# 612_jetracer_esp32s3_030009.net
KiCad netlist of a schematic drawn in EAGLE
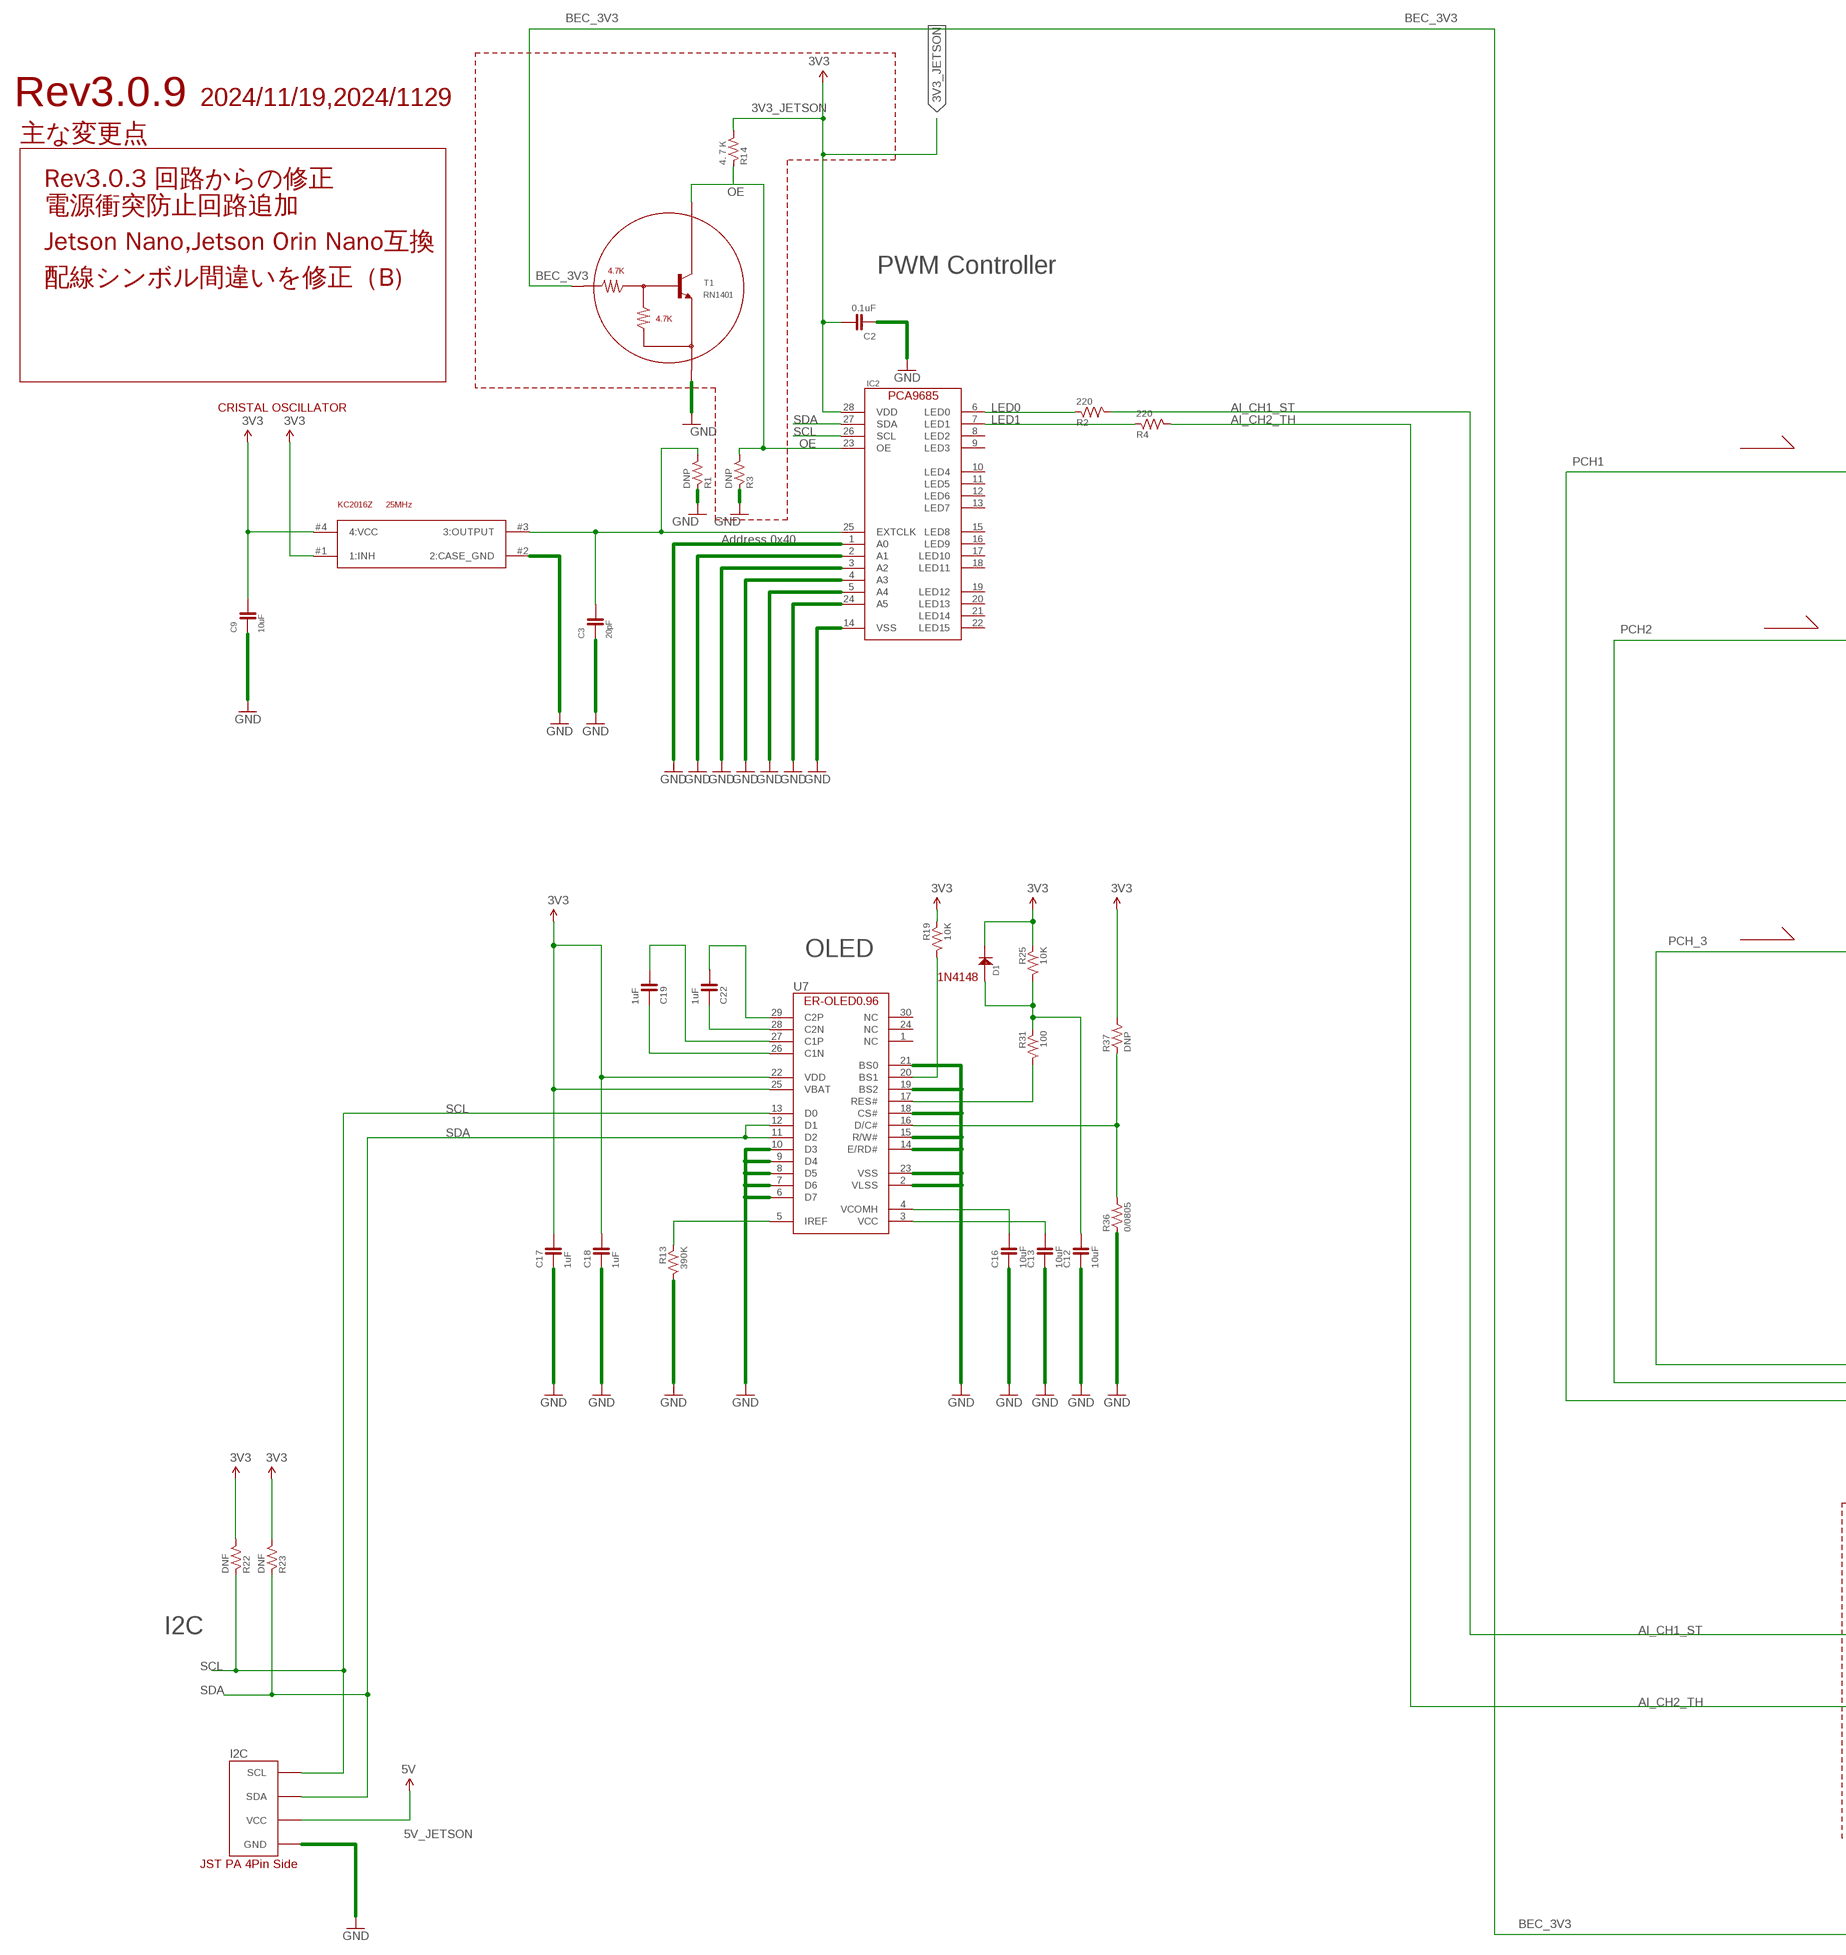
[diagram p0: schematic, sheet 1, part 1 of 3]
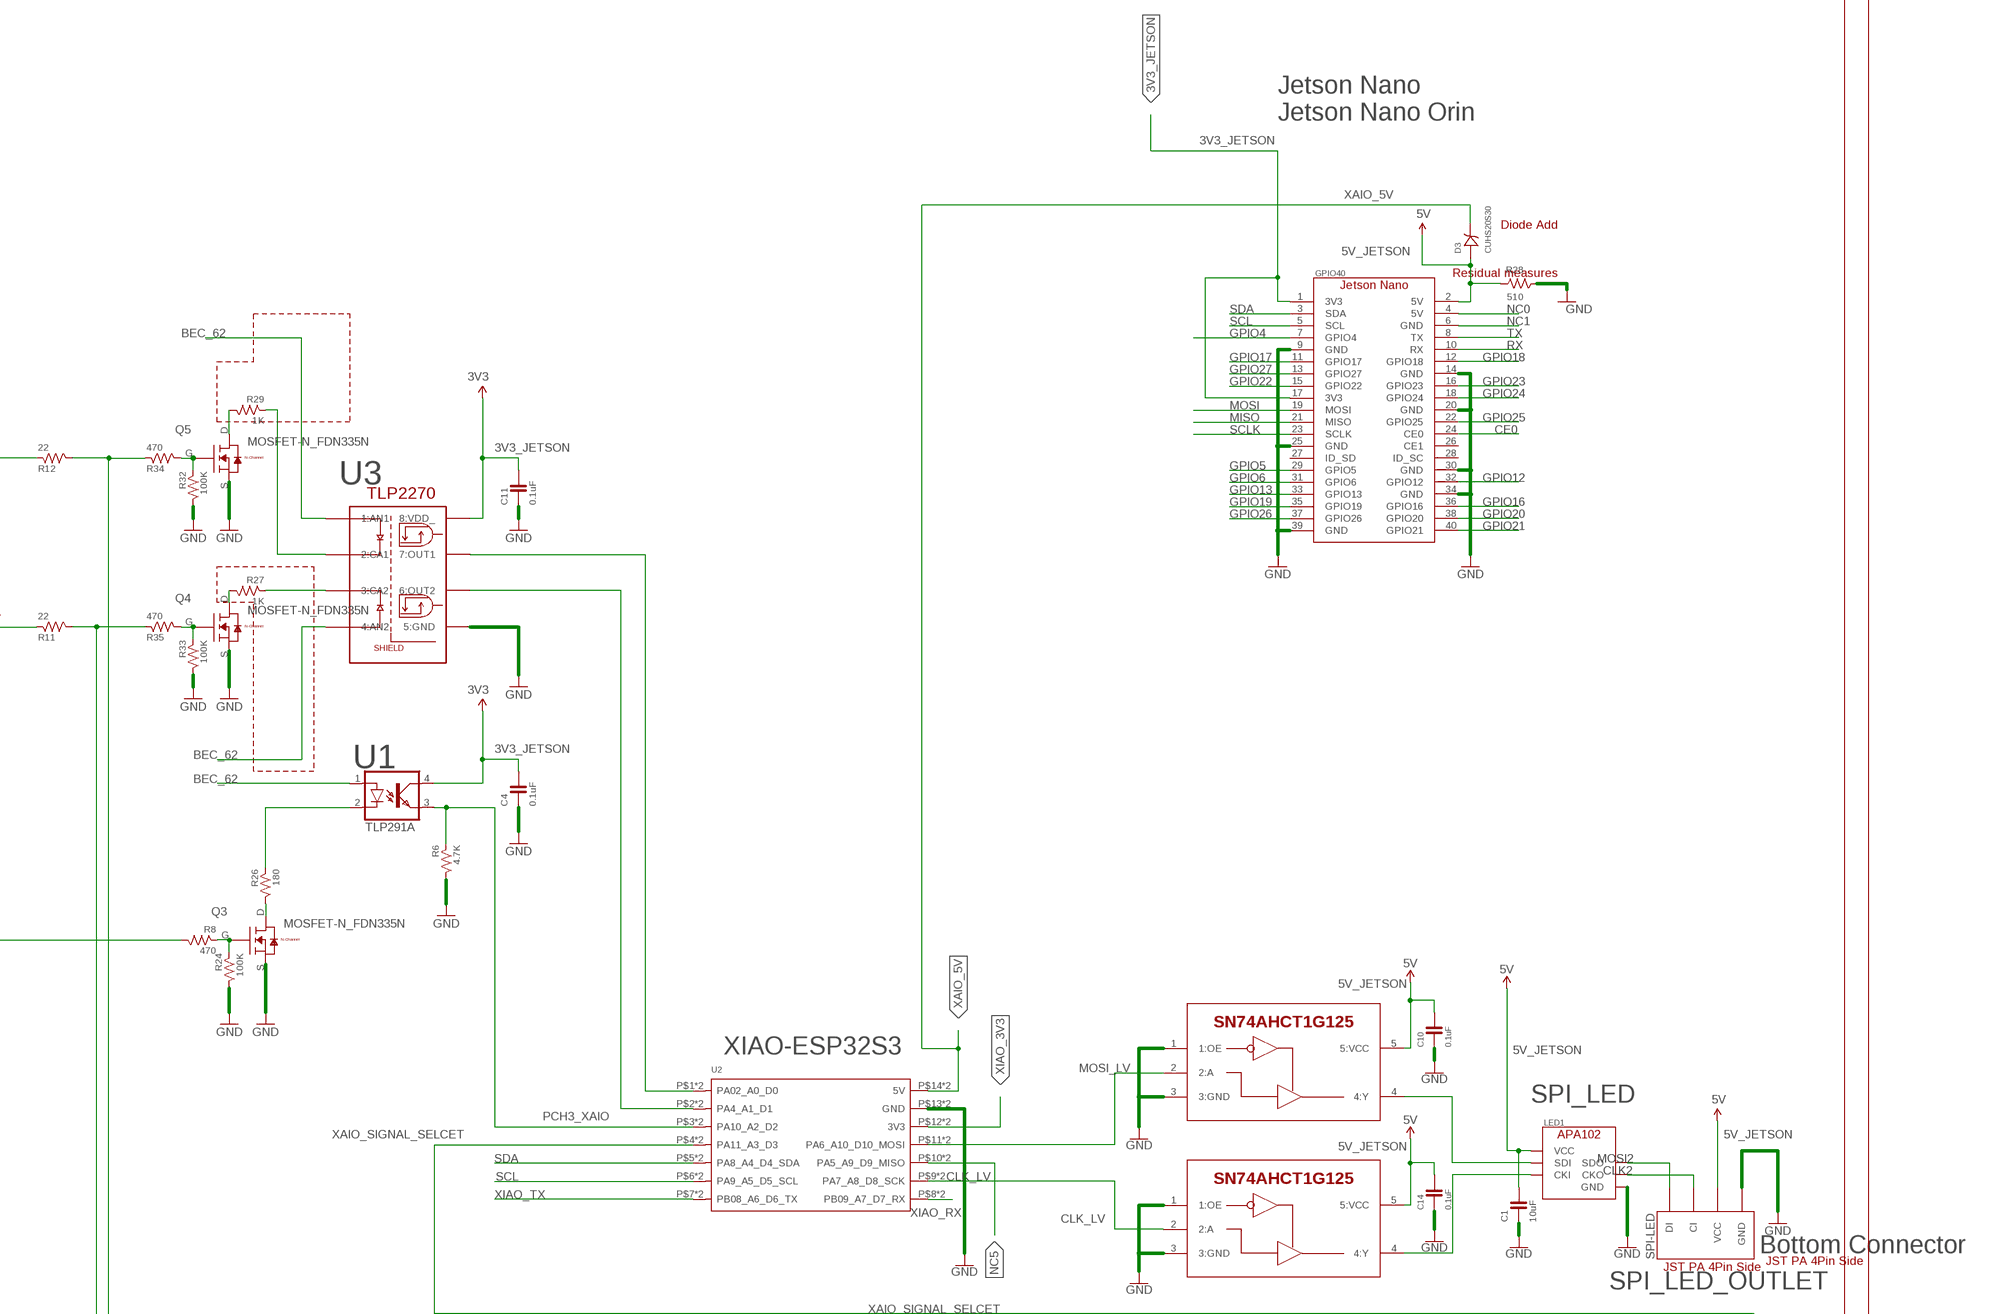
[diagram p1: schematic, sheet 1, part 2 of 3]
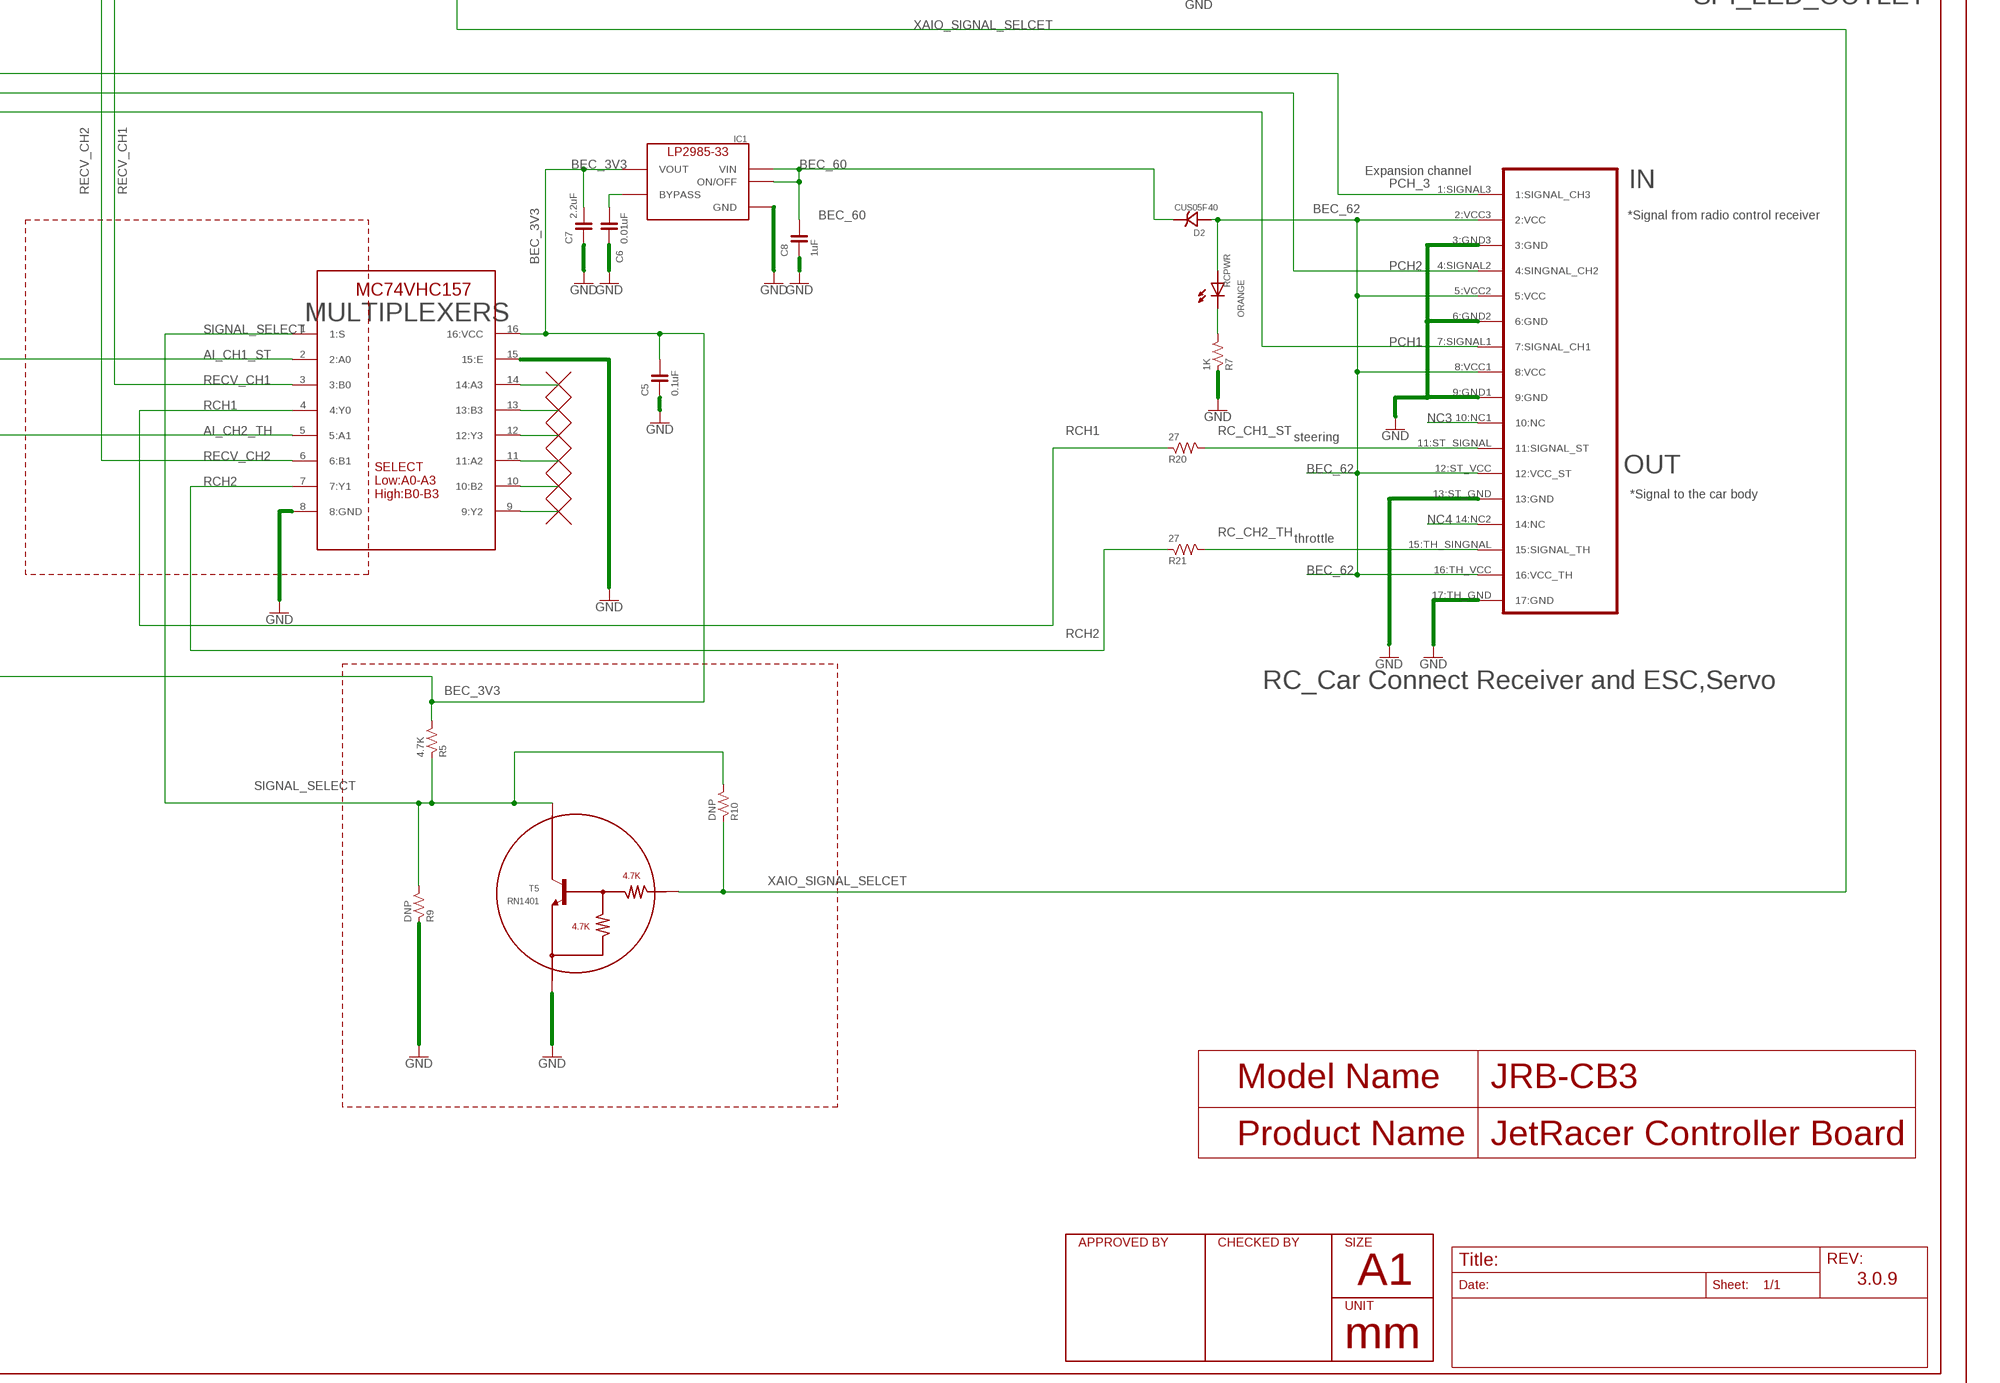
[diagram p2: schematic, sheet 1, part 3 of 3]

(export (version "E")
  (design (tool "Eeschema 10.0.6"))
  (components
    (comp (ref "C1")
      (value "10uF")
      (footprint "eagle-import:0603")
      (libsource (lib "eagle-import") (part "CAPACITOR-0603"))
    )
    (comp (ref "C2")
      (value "0.1uF")
      (footprint "eagle-import:0603")
      (libsource (lib "eagle-import") (part "CAPACITOR-0603"))
    )
    (comp (ref "C3")
      (value "20pF")
      (footprint "eagle-import:0402")
      (libsource (lib "eagle-import") (part "CAPACITOR-0402"))
    )
    (comp (ref "C4")
      (value "0.1uF")
      (footprint "eagle-import:0603")
      (libsource (lib "eagle-import") (part "CAPACITOR-0603"))
    )
    (comp (ref "C5")
      (value "0.1uF")
      (footprint "eagle-import:0603")
      (libsource (lib "eagle-import") (part "CAPACITOR-0603"))
    )
    (comp (ref "C6")
      (value "0.01uF")
      (footprint "eagle-import:0603")
      (libsource (lib "eagle-import") (part "CAPACITOR-0603"))
    )
    (comp (ref "C7")
      (value "2.2uF")
      (footprint "eagle-import:0603")
      (libsource (lib "eagle-import") (part "CAPACITOR-0603"))
    )
    (comp (ref "C8")
      (value "1uF")
      (footprint "eagle-import:0603")
      (libsource (lib "eagle-import") (part "CAPACITOR-0603"))
    )
    (comp (ref "C9")
      (value "10uF")
      (footprint "eagle-import:0402")
      (libsource (lib "eagle-import") (part "CAPACITOR-0402"))
    )
    (comp (ref "C10")
      (value "0.1uF")
      (footprint "eagle-import:0402")
      (libsource (lib "eagle-import") (part "CAPACITOR-0402"))
    )
    (comp (ref "C11")
      (value "0.1uF")
      (footprint "eagle-import:0603")
      (libsource (lib "eagle-import") (part "CAPACITOR-0603"))
    )
    (comp (ref "C12")
      (value "10uF")
      (footprint "eagle-import:0603")
      (libsource (lib "eagle-import") (part "CAPACITOR-0603"))
    )
    (comp (ref "C13")
      (value "10uF")
      (footprint "eagle-import:0603")
      (libsource (lib "eagle-import") (part "CAPACITOR-0603"))
    )
    (comp (ref "C14")
      (value "0.1uF")
      (footprint "eagle-import:0402")
      (libsource (lib "eagle-import") (part "CAPACITOR-0402"))
    )
    (comp (ref "C16")
      (value "10uF")
      (footprint "eagle-import:0603")
      (libsource (lib "eagle-import") (part "CAPACITOR-0603"))
    )
    (comp (ref "C17")
      (value "1uF")
      (footprint "eagle-import:0603")
      (libsource (lib "eagle-import") (part "CAPACITOR-0603"))
    )
    (comp (ref "C18")
      (value "1uF")
      (footprint "eagle-import:0603")
      (libsource (lib "eagle-import") (part "CAPACITOR-0603"))
    )
    (comp (ref "C19")
      (value "1uF")
      (footprint "eagle-import:0603")
      (libsource (lib "eagle-import") (part "CAPACITOR-0603"))
    )
    (comp (ref "C22")
      (value "1uF")
      (footprint "eagle-import:0603")
      (libsource (lib "eagle-import") (part "CAPACITOR-0603"))
    )
    (comp (ref "D1")
      (value "1N4148")
      (footprint "eagle-import:1N4148W")
      (libsource (lib "eagle-import") (part "1N4148"))
    )
    (comp (ref "D2")
      (value "CUS05F40")
      (footprint "eagle-import:CUS05F40")
      (libsource (lib "eagle-import") (part "CUS05F40"))
    )
    (comp (ref "D3")
      (value "CUHS20S30")
      (footprint "eagle-import:US2H")
      (libsource (lib "eagle-import") (part "CUHS20S30"))
    )
    (comp (ref "GPIO40")
      (value "JETSON_NANOJETSON_NANO_OVERALL")
      (footprint "eagle-import:JETSON_NANO_DEMENTION")
      (libsource (lib "eagle-import") (part "JETSON_NANOJETSON_NANO_OVERALL"))
    )
    (comp (ref "I2C")
      (value "FABO-I2C")
      (footprint "eagle-import:I2C-SM04B-PASS-1-FL")
      (libsource (lib "eagle-import") (part "FABO-I2C"))
    )
    (comp (ref "IC1")
      (value "LP2985-33DBVR")
      (footprint "eagle-import:SOT-23-5")
      (libsource (lib "eagle-import") (part "LP2985-33DBVR"))
    )
    (comp (ref "IC2")
      (value "PCA9685PW,BS")
      (footprint "eagle-import:PCA9685")
      (libsource (lib "eagle-import") (part "PCA9685PW,BS"))
    )
    (comp (ref "LED1")
      (value "APA102_IPIXEL")
      (footprint "eagle-import:APA102_2020")
      (libsource (lib "eagle-import") (part "APA102_IPIXEL"))
    )
    (comp (ref "Q3")
      (value "MOSFET-N_FDN335N")
      (footprint "eagle-import:SUPERSOT-3")
      (libsource (lib "eagle-import") (part "MOSFET-N_FDN335N"))
    )
    (comp (ref "Q4")
      (value "MOSFET-N_FDN335N")
      (footprint "eagle-import:SUPERSOT-3")
      (libsource (lib "eagle-import") (part "MOSFET-N_FDN335N"))
    )
    (comp (ref "Q5")
      (value "MOSFET-N_FDN335N")
      (footprint "eagle-import:SUPERSOT-3")
      (libsource (lib "eagle-import") (part "MOSFET-N_FDN335N"))
    )
    (comp (ref "R1")
      (value "DNP")
      (footprint "eagle-import:0603")
      (libsource (lib "eagle-import") (part "RESISTOR-0603"))
    )
    (comp (ref "R2")
      (value "220")
      (footprint "eagle-import:0603")
      (libsource (lib "eagle-import") (part "RESISTOR-0603"))
    )
    (comp (ref "R3")
      (value "DNP")
      (footprint "eagle-import:0603")
      (libsource (lib "eagle-import") (part "RESISTOR-0603"))
    )
    (comp (ref "R4")
      (value "220")
      (footprint "eagle-import:0603")
      (libsource (lib "eagle-import") (part "RESISTOR-0603"))
    )
    (comp (ref "R5")
      (value "4.7K")
      (footprint "eagle-import:0603")
      (fields (field (name "SPICEPREFIX") "R"))
      (libsource (lib "eagle-import") (part "RESISTOR-0603"))
    )
    (comp (ref "R6")
      (value "4.7K")
      (footprint "eagle-import:0603")
      (libsource (lib "eagle-import") (part "RESISTOR-0603"))
    )
    (comp (ref "R7")
      (value "1K")
      (footprint "eagle-import:0603")
      (libsource (lib "eagle-import") (part "RESISTOR-0603"))
    )
    (comp (ref "R8")
      (value "470")
      (footprint "eagle-import:0603")
      (libsource (lib "eagle-import") (part "RESISTOR-0603"))
    )
    (comp (ref "R9")
      (value "DNP")
      (footprint "eagle-import:0603")
      (libsource (lib "eagle-import") (part "RESISTOR-0603"))
    )
    (comp (ref "R10")
      (value "DNP")
      (footprint "eagle-import:0603")
      (libsource (lib "eagle-import") (part "RESISTOR-0603"))
    )
    (comp (ref "R11")
      (value "22")
      (footprint "eagle-import:0603")
      (libsource (lib "eagle-import") (part "RESISTOR-0603"))
    )
    (comp (ref "R12")
      (value "22")
      (footprint "eagle-import:0603")
      (libsource (lib "eagle-import") (part "RESISTOR-0603"))
    )
    (comp (ref "R13")
      (value "390K")
      (footprint "eagle-import:0603")
      (libsource (lib "eagle-import") (part "RESISTOR-0603"))
    )
    (comp (ref "R14")
      (value "4.７K")
      (footprint "eagle-import:0603")
      (libsource (lib "eagle-import") (part "RESISTOR-0603"))
    )
    (comp (ref "R19")
      (value "10K")
      (footprint "eagle-import:0603")
      (libsource (lib "eagle-import") (part "RESISTOR-0603"))
    )
    (comp (ref "R20")
      (value "27")
      (footprint "eagle-import:0603")
      (libsource (lib "eagle-import") (part "RESISTOR-0603"))
    )
    (comp (ref "R21")
      (value "27")
      (footprint "eagle-import:0603")
      (libsource (lib "eagle-import") (part "RESISTOR-0603"))
    )
    (comp (ref "R22")
      (value "DNF")
      (footprint "eagle-import:0603")
      (libsource (lib "eagle-import") (part "RESISTOR-0603"))
    )
    (comp (ref "R23")
      (value "DNF")
      (footprint "eagle-import:0603")
      (libsource (lib "eagle-import") (part "RESISTOR-0603"))
    )
    (comp (ref "R24")
      (value "100K")
      (footprint "eagle-import:0603")
      (libsource (lib "eagle-import") (part "RESISTOR-0603"))
    )
    (comp (ref "R25")
      (value "10K")
      (footprint "eagle-import:0603")
      (libsource (lib "eagle-import") (part "RESISTOR-0603"))
    )
    (comp (ref "R26")
      (value "180")
      (footprint "eagle-import:0603")
      (libsource (lib "eagle-import") (part "RESISTOR-0603"))
    )
    (comp (ref "R27")
      (value "1K")
      (footprint "eagle-import:0603")
      (libsource (lib "eagle-import") (part "RESISTOR-0603"))
    )
    (comp (ref "R28")
      (value "510")
      (footprint "eagle-import:0805")
      (libsource (lib "eagle-import") (part "RESISTOR-0805"))
    )
    (comp (ref "R29")
      (value "1K")
      (footprint "eagle-import:0603")
      (libsource (lib "eagle-import") (part "RESISTOR-0603"))
    )
    (comp (ref "R31")
      (value "100")
      (footprint "eagle-import:0603")
      (libsource (lib "eagle-import") (part "RESISTOR-0603"))
    )
    (comp (ref "R32")
      (value "100K")
      (footprint "eagle-import:0603")
      (libsource (lib "eagle-import") (part "RESISTOR-0603"))
    )
    (comp (ref "R33")
      (value "100K")
      (footprint "eagle-import:0603")
      (libsource (lib "eagle-import") (part "RESISTOR-0603"))
    )
    (comp (ref "R34")
      (value "470")
      (footprint "eagle-import:0603")
      (libsource (lib "eagle-import") (part "RESISTOR-0603"))
    )
    (comp (ref "R35")
      (value "470")
      (footprint "eagle-import:0603")
      (libsource (lib "eagle-import") (part "RESISTOR-0603"))
    )
    (comp (ref "R36")
      (value "0/0805")
      (footprint "eagle-import:0805")
      (libsource (lib "eagle-import") (part "RESISTOR-0805"))
    )
    (comp (ref "R37")
      (value "DNP")
      (footprint "eagle-import:0805")
      (fields (field (name "SPICEPREFIX") "R"))
      (libsource (lib "eagle-import") (part "RESISTOR-0805"))
    )
    (comp (ref "RCPWR")
      (value "ORANGE")
      (footprint "eagle-import:0603")
      (libsource (lib "eagle-import") (part "LED-0603"))
    )
    (comp (ref "SPI-LED")
      (value "FABO-SPI-LED")
      (footprint "eagle-import:SPI-SM04B-PASS-1-FL")
      (libsource (lib "eagle-import") (part "FABO-SPI-LED"))
    )
    (comp (ref "T1")
      (value "RN1401")
      (footprint "eagle-import:SC-59")
      (libsource (lib "eagle-import") (part "RN1401"))
    )
    (comp (ref "T5")
      (value "RN1401")
      (footprint "eagle-import:SC-59")
      (libsource (lib "eagle-import") (part "RN1401"))
    )
    (comp (ref "U$1")
      (value "RC_17PIN_OUTIN")
      (footprint "eagle-import:PNHEADER_2.54_SMT_17PIN_RC_TT01_02")
      (libsource (lib "eagle-import") (part "RC_17PIN_OUTIN"))
    )
    (comp (ref "U$3")
      (value "MC74VHC157")
      (footprint "eagle-import:MC74VHC157_TSSOP-16")
      (libsource (lib "eagle-import") (part "MC74VHC157"))
    )
    (comp (ref "U$9")
      (value "SN74AHCT1G125")
      (footprint "eagle-import:SOT-1DOT1")
      (libsource (lib "eagle-import") (part "SN74AHCT1G125"))
    )
    (comp (ref "U$10")
      (value "SN74AHCT1G125")
      (footprint "eagle-import:SOT-1DOT1")
      (libsource (lib "eagle-import") (part "SN74AHCT1G125"))
    )
    (comp (ref "U$11")
      (value "KC2016Z")
      (footprint "eagle-import:KC2016Z")
      (libsource (lib "eagle-import") (part "KC2016Z"))
    )
    (comp (ref "U1")
      (value "TLP291A")
      (footprint "eagle-import:11-3C1")
      (libsource (lib "eagle-import") (part "TLP291A"))
    )
    (comp (ref "U2")
      (value "MOUDLE-SEEEDUINO-XIAO-ESP32C3")
      (footprint "eagle-import:MOUDLE14P-DIP")
      (libsource (lib "eagle-import") (part "MOUDLE-SEEEDUINO-XIAO-ESP32C3"))
    )
    (comp (ref "U3")
      (value "TLP2270")
      (footprint "eagle-import:TLP2270")
      (libsource (lib "eagle-import") (part "TLP2270"))
    )
    (comp (ref "U7")
      (value "ER-OLED0.96-1ER-CON30HT-1")
      (footprint "eagle-import:ER-CON30HT-1")
      (libsource (lib "eagle-import") (part "ER-OLED0.96-1ER-CON30HT-1"))
    )
  )
  (nets
    (net (code "1") (name "/AI_CH1_ST") (class "Default")
      (node (ref "R2") (pin "2") (pinfunction "2_2") (pintype "bidirectional"))
      (node (ref "U$3") (pin "2") (pinfunction "2:A0_2") (pintype "bidirectional"))
    )
    (net (code "2") (name "/AI_CH2_TH") (class "Default")
      (node (ref "R4") (pin "2") (pinfunction "2_2") (pintype "bidirectional"))
      (node (ref "U$3") (pin "5") (pinfunction "5:A1_5") (pintype "bidirectional"))
    )
    (net (code "3") (name "/BEC_3V3") (class "Default")
      (node (ref "C5") (pin "2") (pinfunction "2_2") (pintype "passive"))
      (node (ref "C7") (pin "2") (pinfunction "2_2") (pintype "passive"))
      (node (ref "IC1") (pin "5") (pinfunction "VOUT_5") (pintype "output"))
      (node (ref "R5") (pin "2") (pinfunction "2_2") (pintype "bidirectional"))
      (node (ref "T1") (pin "B") (pinfunction "B_B") (pintype "passive"))
      (node (ref "U$3") (pin "16") (pinfunction "16:VCC_16") (pintype "bidirectional"))
    )
    (net (code "4") (name "/BEC_60") (class "Default")
      (node (ref "C8") (pin "2") (pinfunction "2_2") (pintype "passive"))
      (node (ref "D2") (pin "C") (pinfunction "CATHODE_C") (pintype "bidirectional"))
      (node (ref "IC1") (pin "1") (pinfunction "VIN_1") (pintype "input"))
      (node (ref "IC1") (pin "3") (pinfunction "ON/OFF_3") (pintype "input"))
    )
    (net (code "5") (name "/BEC_62") (class "Default")
      (node (ref "D2") (pin "A") (pinfunction "ANODE_A") (pintype "bidirectional"))
      (node (ref "RCPWR") (pin "ANODE") (pinfunction "ANODE_ANODE") (pintype "passive"))
      (node (ref "U$1") (pin "12:ST_VCC") (pinfunction "12:VCC_ST_12:ST_VCC") (pintype "bidirectional"))
      (node (ref "U$1") (pin "16:TH_VCC") (pinfunction "16:VCC_TH_16:TH_VCC") (pintype "bidirectional"))
      (node (ref "U$1") (pin "2:VCC3") (pinfunction "2:VCC_2:VCC3") (pintype "bidirectional"))
      (node (ref "U$1") (pin "5:VCC2") (pinfunction "5:VCC_5:VCC2") (pintype "bidirectional"))
      (node (ref "U$1") (pin "8:VCC1") (pinfunction "8:VCC_8:VCC1") (pintype "bidirectional"))
      (node (ref "U1") (pin "1") (pinfunction "A_1") (pintype "passive"))
      (node (ref "U3") (pin "1") (pinfunction "1:AN1_1") (pintype "bidirectional"))
      (node (ref "U3") (pin "4") (pinfunction "4:AN2_4") (pintype "bidirectional"))
    )
    (net (code "6") (name "/CE0") (class "Default")
      (node (ref "GPIO40") (pin "24") (pinfunction "CE0_24") (pintype "bidirectional"))
    )
    (net (code "7") (name "/CLK2") (class "Default")
      (node (ref "LED1") (pin "CKO") (pinfunction "CKO_CKO") (pintype "bidirectional"))
      (node (ref "SPI-LED") (pin "CI") (pinfunction "CI_CI") (pintype "bidirectional"))
    )
    (net (code "8") (name "/CLK_LV") (class "Default")
      (node (ref "U$10") (pin "2") (pinfunction "2:A_2") (pintype "input"))
      (node (ref "U2") (pin "P$23") (pinfunction "PA7_A8_D8_SCK_P$23") (pintype "bidirectional"))
      (node (ref "U2") (pin "P$9") (pinfunction "PA7_A8_D8_SCK_P$9") (pintype "bidirectional"))
    )
    (net (code "9") (name "/GPIO4") (class "Default")
      (node (ref "GPIO40") (pin "7") (pinfunction "GPIO4_7") (pintype "bidirectional"))
    )
    (net (code "10") (name "/GPIO5") (class "Default")
      (node (ref "GPIO40") (pin "29") (pinfunction "GPIO5_29") (pintype "bidirectional"))
    )
    (net (code "11") (name "/GPIO6") (class "Default")
      (node (ref "GPIO40") (pin "31") (pinfunction "GPIO6_31") (pintype "bidirectional"))
    )
    (net (code "12") (name "/GPIO12") (class "Default")
      (node (ref "GPIO40") (pin "32") (pinfunction "GPIO12_32") (pintype "bidirectional"))
    )
    (net (code "13") (name "/GPIO13") (class "Default")
      (node (ref "GPIO40") (pin "33") (pinfunction "GPIO13_33") (pintype "bidirectional"))
    )
    (net (code "14") (name "/GPIO16") (class "Default")
      (node (ref "GPIO40") (pin "36") (pinfunction "GPIO16_36") (pintype "bidirectional"))
    )
    (net (code "15") (name "/GPIO17") (class "Default")
      (node (ref "GPIO40") (pin "11") (pinfunction "GPIO17_11") (pintype "bidirectional"))
    )
    (net (code "16") (name "/GPIO18") (class "Default")
      (node (ref "GPIO40") (pin "12") (pinfunction "GPIO18_12") (pintype "bidirectional"))
    )
    (net (code "17") (name "/GPIO19") (class "Default")
      (node (ref "GPIO40") (pin "35") (pinfunction "GPIO19_35") (pintype "bidirectional"))
    )
    (net (code "18") (name "/GPIO20") (class "Default")
      (node (ref "GPIO40") (pin "38") (pinfunction "GPIO20_38") (pintype "bidirectional"))
    )
    (net (code "19") (name "/GPIO21") (class "Default")
      (node (ref "GPIO40") (pin "40") (pinfunction "GPIO21_40") (pintype "bidirectional"))
    )
    (net (code "20") (name "/GPIO22") (class "Default")
      (node (ref "GPIO40") (pin "15") (pinfunction "GPIO22_15") (pintype "bidirectional"))
    )
    (net (code "21") (name "/GPIO23") (class "Default")
      (node (ref "GPIO40") (pin "16") (pinfunction "GPIO23_16") (pintype "bidirectional"))
    )
    (net (code "22") (name "/GPIO24") (class "Default")
      (node (ref "GPIO40") (pin "18") (pinfunction "GPIO24_18") (pintype "bidirectional"))
    )
    (net (code "23") (name "/GPIO25") (class "Default")
      (node (ref "GPIO40") (pin "22") (pinfunction "GPIO25_22") (pintype "bidirectional"))
    )
    (net (code "24") (name "/GPIO26") (class "Default")
      (node (ref "GPIO40") (pin "37") (pinfunction "GPIO26_37") (pintype "bidirectional"))
    )
    (net (code "25") (name "/GPIO27") (class "Default")
      (node (ref "GPIO40") (pin "13") (pinfunction "GPIO27_13") (pintype "bidirectional"))
    )
    (net (code "26") (name "/LED0") (class "Default")
      (node (ref "IC2") (pin "6") (pinfunction "LED0_6") (pintype "bidirectional"))
      (node (ref "R2") (pin "1") (pinfunction "1_1") (pintype "bidirectional"))
    )
    (net (code "27") (name "/LED1") (class "Default")
      (node (ref "IC2") (pin "7") (pinfunction "LED1_7") (pintype "bidirectional"))
      (node (ref "R4") (pin "1") (pinfunction "1_1") (pintype "bidirectional"))
    )
    (net (code "28") (name "/MISO") (class "Default")
      (node (ref "GPIO40") (pin "21") (pinfunction "MISO_21") (pintype "bidirectional"))
    )
    (net (code "29") (name "/MOSI") (class "Default")
      (node (ref "GPIO40") (pin "19") (pinfunction "MOSI_19") (pintype "bidirectional"))
    )
    (net (code "30") (name "/MOSI2") (class "Default")
      (node (ref "LED1") (pin "SDO") (pinfunction "SDO_SDO") (pintype "bidirectional"))
      (node (ref "SPI-LED") (pin "DI") (pinfunction "DI_DI") (pintype "bidirectional"))
    )
    (net (code "31") (name "/MOSI_LV") (class "Default")
      (node (ref "U$9") (pin "2") (pinfunction "2:A_2") (pintype "input"))
      (node (ref "U2") (pin "P$11") (pinfunction "PA6_A10_D10_MOSI_P$11") (pintype "bidirectional"))
      (node (ref "U2") (pin "P$25") (pinfunction "PA6_A10_D10_MOSI_P$25") (pintype "bidirectional"))
    )
    (net (code "32") (name "/NC0") (class "Default")
      (node (ref "GPIO40") (pin "4") (pinfunction "5V_4") (pintype "bidirectional"))
    )
    (net (code "33") (name "/NC1") (class "Default")
      (node (ref "GPIO40") (pin "6") (pinfunction "GND_6") (pintype "bidirectional"))
    )
    (net (code "34") (name "/NC3") (class "Default")
      (node (ref "U$1") (pin "10:NC1") (pinfunction "10:NC_10:NC1") (pintype "bidirectional"))
    )
    (net (code "35") (name "/NC4") (class "Default")
      (node (ref "U$1") (pin "14:NC2") (pinfunction "14:NC_14:NC2") (pintype "bidirectional"))
    )
    (net (code "36") (name "/OE") (class "Default")
      (node (ref "IC2") (pin "23") (pinfunction "OE_23") (pintype "bidirectional"))
      (node (ref "R14") (pin "1") (pinfunction "1_1") (pintype "bidirectional"))
      (node (ref "R3") (pin "2") (pinfunction "2_2") (pintype "bidirectional"))
      (node (ref "T1") (pin "C") (pinfunction "C_C") (pintype "passive"))
    )
    (net (code "37") (name "/PCH1") (class "Default")
      (node (ref "R12") (pin "1") (pinfunction "1_1") (pintype "bidirectional"))
      (node (ref "U$1") (pin "7:SIGNAL1") (pinfunction "7:SIGNAL_CH1_7:SIGNAL1") (pintype "bidirectional"))
    )
    (net (code "38") (name "/PCH2") (class "Default")
      (node (ref "R11") (pin "1") (pinfunction "1_1") (pintype "bidirectional"))
      (node (ref "U$1") (pin "4:SIGNAL2") (pinfunction "4:SINGNAL_CH2_4:SIGNAL2") (pintype "bidirectional"))
    )
    (net (code "39") (name "/PCH3_XAIO") (class "Default")
      (node (ref "R6") (pin "1") (pinfunction "1_1") (pintype "bidirectional"))
      (node (ref "U1") (pin "3") (pinfunction "EMI_3") (pintype "passive"))
      (node (ref "U2") (pin "P$17") (pinfunction "PA10_A2_D2_P$17") (pintype "bidirectional"))
      (node (ref "U2") (pin "P$3") (pinfunction "PA10_A2_D2_P$3") (pintype "bidirectional"))
    )
    (net (code "40") (name "/PCH_3") (class "Default")
      (node (ref "R8") (pin "2") (pinfunction "2_2") (pintype "bidirectional"))
      (node (ref "U$1") (pin "1:SIGNAL3") (pinfunction "1:SIGNAL_CH3_1:SIGNAL3") (pintype "bidirectional"))
    )
    (net (code "41") (name "/RCH1") (class "Default")
      (node (ref "R20") (pin "1") (pinfunction "1_1") (pintype "bidirectional"))
      (node (ref "U$3") (pin "4") (pinfunction "4:Y0_4") (pintype "bidirectional"))
    )
    (net (code "42") (name "/RCH2") (class "Default")
      (node (ref "R21") (pin "1") (pinfunction "1_1") (pintype "bidirectional"))
      (node (ref "U$3") (pin "7") (pinfunction "7:Y1_7") (pintype "bidirectional"))
    )
    (net (code "43") (name "/RC_CH1_ST") (class "Default")
      (node (ref "R20") (pin "2") (pinfunction "2_2") (pintype "bidirectional"))
      (node (ref "U$1") (pin "11:ST_SIGNAL") (pinfunction "11:SIGNAL_ST_11:ST_SIGNAL") (pintype "bidirectional"))
    )
    (net (code "44") (name "/RC_CH2_TH") (class "Default")
      (node (ref "R21") (pin "2") (pinfunction "2_2") (pintype "bidirectional"))
      (node (ref "U$1") (pin "15:TH_SINGNAL") (pinfunction "15:SIGNAL_TH_15:TH_SINGNAL") (pintype "bidirectional"))
    )
    (net (code "45") (name "/RECV_CH1") (class "Default")
      (node (ref "R12") (pin "2") (pinfunction "2_2") (pintype "bidirectional"))
      (node (ref "R34") (pin "1") (pinfunction "1_1") (pintype "bidirectional"))
      (node (ref "U$3") (pin "3") (pinfunction "3:B0_3") (pintype "bidirectional"))
    )
    (net (code "46") (name "/RECV_CH2") (class "Default")
      (node (ref "R11") (pin "2") (pinfunction "2_2") (pintype "bidirectional"))
      (node (ref "R35") (pin "1") (pinfunction "1_1") (pintype "bidirectional"))
      (node (ref "U$3") (pin "6") (pinfunction "6:B1_6") (pintype "bidirectional"))
    )
    (net (code "47") (name "/RX") (class "Default")
      (node (ref "GPIO40") (pin "10") (pinfunction "RX_10") (pintype "bidirectional"))
    )
    (net (code "48") (name "/SCL") (class "Default")
      (node (ref "GPIO40") (pin "5") (pinfunction "SCL_5") (pintype "bidirectional"))
      (node (ref "I2C") (pin "SCL") (pinfunction "SCL_SCL") (pintype "bidirectional"))
      (node (ref "IC2") (pin "26") (pinfunction "SCL_26") (pintype "bidirectional"))
      (node (ref "R22") (pin "1") (pinfunction "1_1") (pintype "bidirectional"))
      (node (ref "U2") (pin "P$20") (pinfunction "PA9_A5_D5_SCL_P$20") (pintype "bidirectional"))
      (node (ref "U2") (pin "P$6") (pinfunction "PA9_A5_D5_SCL_P$6") (pintype "bidirectional"))
      (node (ref "U7") (pin "13") (pinfunction "D0_13") (pintype "bidirectional"))
    )
    (net (code "49") (name "/SCLK") (class "Default")
      (node (ref "GPIO40") (pin "23") (pinfunction "SCLK_23") (pintype "bidirectional"))
    )
    (net (code "50") (name "/SDA") (class "Default")
      (node (ref "GPIO40") (pin "3") (pinfunction "SDA_3") (pintype "bidirectional"))
      (node (ref "I2C") (pin "SDA") (pinfunction "SDA_SDA") (pintype "bidirectional"))
      (node (ref "IC2") (pin "27") (pinfunction "SDA_27") (pintype "bidirectional"))
      (node (ref "R23") (pin "1") (pinfunction "1_1") (pintype "bidirectional"))
      (node (ref "U2") (pin "P$19") (pinfunction "PA8_A4_D4_SDA_P$19") (pintype "bidirectional"))
      (node (ref "U2") (pin "P$5") (pinfunction "PA8_A4_D4_SDA_P$5") (pintype "bidirectional"))
      (node (ref "U7") (pin "11") (pinfunction "D2_11") (pintype "bidirectional"))
      (node (ref "U7") (pin "12") (pinfunction "D1_12") (pintype "bidirectional"))
    )
    (net (code "51") (name "/SIGNAL_SELECT") (class "Default")
      (node (ref "R10") (pin "2") (pinfunction "2_2") (pintype "bidirectional"))
      (node (ref "R5") (pin "1") (pinfunction "1_1") (pintype "bidirectional"))
      (node (ref "R9") (pin "2") (pinfunction "2_2") (pintype "bidirectional"))
      (node (ref "T5") (pin "C") (pinfunction "C_C") (pintype "passive"))
      (node (ref "U$3") (pin "1") (pinfunction "1:S_1") (pintype "bidirectional"))
    )
    (net (code "52") (name "/TX") (class "Default")
      (node (ref "GPIO40") (pin "8") (pinfunction "TX_8") (pintype "bidirectional"))
    )
    (net (code "53") (name "/XAIO_SIGNAL_SELCET") (class "Default")
      (node (ref "R10") (pin "1") (pinfunction "1_1") (pintype "bidirectional"))
      (node (ref "T5") (pin "B") (pinfunction "B_B") (pintype "passive"))
      (node (ref "U2") (pin "P$18") (pinfunction "PA11_A3_D3_P$18") (pintype "bidirectional"))
      (node (ref "U2") (pin "P$4") (pinfunction "PA11_A3_D3_P$4") (pintype "bidirectional"))
    )
    (net (code "54") (name "/XIAO_RX") (class "Default")
      (node (ref "U2") (pin "P$22") (pinfunction "PB09_A7_D7_RX_P$22") (pintype "bidirectional"))
      (node (ref "U2") (pin "P$8") (pinfunction "PB09_A7_D7_RX_P$8") (pintype "bidirectional"))
    )
    (net (code "55") (name "/XIAO_TX") (class "Default")
      (node (ref "U2") (pin "P$21") (pinfunction "PB08_A6_D6_TX_P$21") (pintype "bidirectional"))
      (node (ref "U2") (pin "P$7") (pinfunction "PB08_A6_D6_TX_P$7") (pintype "bidirectional"))
    )
    (net (code "56") (name "3V3_JETSON") (class "Default")
      (node (ref "C11") (pin "2") (pinfunction "2_2") (pintype "passive"))
      (node (ref "C17") (pin "2") (pinfunction "2_2") (pintype "passive"))
      (node (ref "C18") (pin "2") (pinfunction "2_2") (pintype "passive"))
      (node (ref "C2") (pin "2") (pinfunction "2_2") (pintype "passive"))
      (node (ref "C4") (pin "2") (pinfunction "2_2") (pintype "passive"))
      (node (ref "C9") (pin "2") (pinfunction "2_2") (pintype "passive"))
      (node (ref "D1") (pin "CATHODE") (pinfunction "CATHODE_CATHODE") (pintype "bidirectional"))
      (node (ref "GPIO40") (pin "1") (pinfunction "3V3_1") (pintype "bidirectional"))
      (node (ref "GPIO40") (pin "17") (pinfunction "3V3_17") (pintype "bidirectional"))
      (node (ref "IC2") (pin "28") (pinfunction "VDD_28") (pintype "bidirectional"))
      (node (ref "R14") (pin "2") (pinfunction "2_2") (pintype "bidirectional"))
      (node (ref "R19") (pin "1") (pinfunction "1_1") (pintype "bidirectional"))
      (node (ref "R22") (pin "2") (pinfunction "2_2") (pintype "bidirectional"))
      (node (ref "R23") (pin "2") (pinfunction "2_2") (pintype "bidirectional"))
      (node (ref "R25") (pin "1") (pinfunction "1_1") (pintype "bidirectional"))
      (node (ref "R37") (pin "2") (pinfunction "2_2") (pintype "bidirectional"))
      (node (ref "U$11") (pin "#1") (pinfunction "1:INH_#1") (pintype "bidirectional"))
      (node (ref "U$11") (pin "#4") (pinfunction "4:VCC_#4") (pintype "bidirectional"))
      (node (ref "U1") (pin "4") (pinfunction "COL_4") (pintype "passive"))
      (node (ref "U3") (pin "8") (pinfunction "8:VDD__8") (pintype "bidirectional"))
      (node (ref "U7") (pin "22") (pinfunction "VDD_22") (pintype "bidirectional"))
      (node (ref "U7") (pin "25") (pinfunction "VBAT_25") (pintype "bidirectional"))
    )
    (net (code "57") (name "5V") (class "Default")
      (node (ref "C1") (pin "2") (pinfunction "2_2") (pintype "passive"))
      (node (ref "C10") (pin "2") (pinfunction "2_2") (pintype "passive"))
      (node (ref "C14") (pin "2") (pinfunction "2_2") (pintype "passive"))
      (node (ref "D3") (pin "A") (pinfunction "ANODE_A") (pintype "passive"))
      (node (ref "GPIO40") (pin "2") (pinfunction "5V_2") (pintype "bidirectional"))
      (node (ref "I2C") (pin "5V") (pinfunction "VCC_5V") (pintype "bidirectional"))
      (node (ref "LED1") (pin "VCC") (pinfunction "VCC_VCC") (pintype "bidirectional"))
      (node (ref "R28") (pin "2") (pinfunction "2_2") (pintype "bidirectional"))
      (node (ref "SPI-LED") (pin "5V") (pinfunction "VCC_5V") (pintype "bidirectional"))
      (node (ref "U$10") (pin "5") (pinfunction "5:VCC_5") (pintype "power_in"))
      (node (ref "U$9") (pin "5") (pinfunction "5:VCC_5") (pintype "power_in"))
    )
    (net (code "58") (name "GND") (class "Default")
      (node (ref "C1") (pin "1") (pinfunction "1_1") (pintype "passive"))
      (node (ref "C10") (pin "1") (pinfunction "1_1") (pintype "passive"))
      (node (ref "C11") (pin "1") (pinfunction "1_1") (pintype "passive"))
      (node (ref "C12") (pin "1") (pinfunction "1_1") (pintype "passive"))
      (node (ref "C13") (pin "1") (pinfunction "1_1") (pintype "passive"))
      (node (ref "C14") (pin "1") (pinfunction "1_1") (pintype "passive"))
      (node (ref "C16") (pin "1") (pinfunction "1_1") (pintype "passive"))
      (node (ref "C17") (pin "1") (pinfunction "1_1") (pintype "passive"))
      (node (ref "C18") (pin "1") (pinfunction "1_1") (pintype "passive"))
      (node (ref "C2") (pin "1") (pinfunction "1_1") (pintype "passive"))
      (node (ref "C3") (pin "1") (pinfunction "1_1") (pintype "passive"))
      (node (ref "C4") (pin "1") (pinfunction "1_1") (pintype "passive"))
      (node (ref "C5") (pin "1") (pinfunction "1_1") (pintype "passive"))
      (node (ref "C6") (pin "1") (pinfunction "1_1") (pintype "passive"))
      (node (ref "C7") (pin "1") (pinfunction "1_1") (pintype "passive"))
      (node (ref "C8") (pin "1") (pinfunction "1_1") (pintype "passive"))
      (node (ref "C9") (pin "1") (pinfunction "1_1") (pintype "passive"))
      (node (ref "GPIO40") (pin "14") (pinfunction "GND_14") (pintype "bidirectional"))
      (node (ref "GPIO40") (pin "20") (pinfunction "GND_20") (pintype "bidirectional"))
      (node (ref "GPIO40") (pin "25") (pinfunction "GND_25") (pintype "bidirectional"))
      (node (ref "GPIO40") (pin "30") (pinfunction "GND_30") (pintype "bidirectional"))
      (node (ref "GPIO40") (pin "34") (pinfunction "GND_34") (pintype "bidirectional"))
      (node (ref "GPIO40") (pin "39") (pinfunction "GND_39") (pintype "bidirectional"))
      (node (ref "GPIO40") (pin "9") (pinfunction "GND_9") (pintype "bidirectional"))
      (node (ref "I2C") (pin "GND") (pinfunction "GND_GND") (pintype "bidirectional"))
      (node (ref "IC1") (pin "2") (pinfunction "GND_2") (pintype "power_in"))
      (node (ref "IC2") (pin "1") (pinfunction "A0_1") (pintype "bidirectional"))
      (node (ref "IC2") (pin "14") (pinfunction "VSS_14") (pintype "bidirectional"))
      (node (ref "IC2") (pin "2") (pinfunction "A1_2") (pintype "bidirectional"))
      (node (ref "IC2") (pin "24") (pinfunction "A5_24") (pintype "bidirectional"))
      (node (ref "IC2") (pin "3") (pinfunction "A2_3") (pintype "bidirectional"))
      (node (ref "IC2") (pin "4") (pinfunction "A3_4") (pintype "bidirectional"))
      (node (ref "IC2") (pin "5") (pinfunction "A4_5") (pintype "bidirectional"))
      (node (ref "LED1") (pin "GND") (pinfunction "GND_GND") (pintype "bidirectional"))
      (node (ref "Q3") (pin "S") (pinfunction "S_S") (pintype "passive"))
      (node (ref "Q4") (pin "S") (pinfunction "S_S") (pintype "passive"))
      (node (ref "Q5") (pin "S") (pinfunction "S_S") (pintype "passive"))
      (node (ref "R1") (pin "1") (pinfunction "1_1") (pintype "bidirectional"))
      (node (ref "R13") (pin "2") (pinfunction "2_2") (pintype "bidirectional"))
      (node (ref "R24") (pin "2") (pinfunction "2_2") (pintype "bidirectional"))
      (node (ref "R28") (pin "1") (pinfunction "1_1") (pintype "bidirectional"))
      (node (ref "R3") (pin "1") (pinfunction "1_1") (pintype "bidirectional"))
      (node (ref "R32") (pin "2") (pinfunction "2_2") (pintype "bidirectional"))
      (node (ref "R33") (pin "2") (pinfunction "2_2") (pintype "bidirectional"))
      (node (ref "R36") (pin "1") (pinfunction "1_1") (pintype "bidirectional"))
      (node (ref "R6") (pin "2") (pinfunction "2_2") (pintype "bidirectional"))
      (node (ref "R7") (pin "1") (pinfunction "1_1") (pintype "bidirectional"))
      (node (ref "R9") (pin "1") (pinfunction "1_1") (pintype "bidirectional"))
      (node (ref "SPI-LED") (pin "GND") (pinfunction "GND_GND") (pintype "bidirectional"))
      (node (ref "T1") (pin "E") (pinfunction "E_E") (pintype "passive"))
      (node (ref "T5") (pin "E") (pinfunction "E_E") (pintype "passive"))
      (node (ref "U$1") (pin "13:ST_GND") (pinfunction "13:GND_13:ST_GND") (pintype "bidirectional"))
      (node (ref "U$1") (pin "17:TH_GND") (pinfunction "17:GND_17:TH_GND") (pintype "bidirectional"))
      (node (ref "U$1") (pin "3:GND3") (pinfunction "3:GND_3:GND3") (pintype "bidirectional"))
      (node (ref "U$1") (pin "6:GND2") (pinfunction "6:GND_6:GND2") (pintype "bidirectional"))
      (node (ref "U$1") (pin "9:GND1") (pinfunction "9:GND_9:GND1") (pintype "bidirectional"))
      (node (ref "U$10") (pin "1") (pinfunction "1:OE_1") (pintype "input"))
      (node (ref "U$10") (pin "3") (pinfunction "3:GND_3") (pintype "power_in"))
      (node (ref "U$11") (pin "#2") (pinfunction "2:CASE_GND_#2") (pintype "bidirectional"))
      (node (ref "U$3") (pin "15") (pinfunction "15:E_15") (pintype "bidirectional"))
      (node (ref "U$3") (pin "8") (pinfunction "8:GND_8") (pintype "bidirectional"))
      (node (ref "U$9") (pin "1") (pinfunction "1:OE_1") (pintype "input"))
      (node (ref "U$9") (pin "3") (pinfunction "3:GND_3") (pintype "power_in"))
      (node (ref "U2") (pin "P$13") (pinfunction "GND_P$13") (pintype "bidirectional"))
      (node (ref "U2") (pin "P$27") (pinfunction "GND_P$27") (pintype "bidirectional"))
      (node (ref "U3") (pin "5") (pinfunction "5:GND_5") (pintype "bidirectional"))
      (node (ref "U7") (pin "10") (pinfunction "D3_10") (pintype "bidirectional"))
      (node (ref "U7") (pin "14") (pinfunction "E/RD#_14") (pintype "bidirectional"))
      (node (ref "U7") (pin "15") (pinfunction "R/W#_15") (pintype "bidirectional"))
      (node (ref "U7") (pin "18") (pinfunction "CS#_18") (pintype "bidirectional"))
      (node (ref "U7") (pin "19") (pinfunction "BS2_19") (pintype "bidirectional"))
      (node (ref "U7") (pin "2") (pinfunction "VLSS_2") (pintype "bidirectional"))
      (node (ref "U7") (pin "21") (pinfunction "BS0_21") (pintype "bidirectional"))
      (node (ref "U7") (pin "23") (pinfunction "VSS_23") (pintype "bidirectional"))
      (node (ref "U7") (pin "6") (pinfunction "D7_6") (pintype "bidirectional"))
      (node (ref "U7") (pin "7") (pinfunction "D6_7") (pintype "bidirectional"))
      (node (ref "U7") (pin "8") (pinfunction "D5_8") (pintype "bidirectional"))
      (node (ref "U7") (pin "9") (pinfunction "D4_9") (pintype "bidirectional"))
    )
    (net (code "59") (name "NC5") (class "Default")
      (node (ref "U2") (pin "P$10") (pinfunction "PA5_A9_D9_MISO_P$10") (pintype "bidirectional"))
      (node (ref "U2") (pin "P$24") (pinfunction "PA5_A9_D9_MISO_P$24") (pintype "bidirectional"))
    )
    (net (code "60") (name "Net-(C12-Pad2)") (class "Default")
      (node (ref "C12") (pin "2") (pinfunction "2_2") (pintype "passive"))
      (node (ref "D1") (pin "ANODE") (pinfunction "ANODE_ANODE") (pintype "bidirectional"))
      (node (ref "R25") (pin "2") (pinfunction "2_2") (pintype "bidirectional"))
      (node (ref "R31") (pin "1") (pinfunction "1_1") (pintype "bidirectional"))
    )
    (net (code "61") (name "Net-(IC1-BYPASS)") (class "Default")
      (node (ref "C6") (pin "2") (pinfunction "2_2") (pintype "passive"))
      (node (ref "IC1") (pin "4") (pinfunction "BYPASS_4") (pintype "bidirectional"))
    )
    (net (code "62") (name "Net-(IC2-EXTCLK)") (class "Default")
      (node (ref "C3") (pin "2") (pinfunction "2_2") (pintype "passive"))
      (node (ref "IC2") (pin "25") (pinfunction "EXTCLK_25") (pintype "bidirectional"))
      (node (ref "R1") (pin "2") (pinfunction "2_2") (pintype "bidirectional"))
      (node (ref "U$11") (pin "#3") (pinfunction "3:OUTPUT_#3") (pintype "bidirectional"))
    )
    (net (code "63") (name "Net-(Q3-PadD)") (class "Default")
      (node (ref "Q3") (pin "D") (pinfunction "D_D") (pintype "passive"))
      (node (ref "R26") (pin "2") (pinfunction "2_2") (pintype "bidirectional"))
    )
    (net (code "64") (name "Net-(Q3-PadG)") (class "Default")
      (node (ref "Q3") (pin "G") (pinfunction "G_G") (pintype "passive"))
      (node (ref "R24") (pin "1") (pinfunction "1_1") (pintype "bidirectional"))
      (node (ref "R8") (pin "1") (pinfunction "1_1") (pintype "bidirectional"))
    )
    (net (code "65") (name "Net-(Q4-PadD)") (class "Default")
      (node (ref "Q4") (pin "D") (pinfunction "D_D") (pintype "passive"))
      (node (ref "R27") (pin "2") (pinfunction "2_2") (pintype "bidirectional"))
    )
    (net (code "66") (name "Net-(Q4-PadG)") (class "Default")
      (node (ref "Q4") (pin "G") (pinfunction "G_G") (pintype "passive"))
      (node (ref "R33") (pin "1") (pinfunction "1_1") (pintype "bidirectional"))
      (node (ref "R35") (pin "2") (pinfunction "2_2") (pintype "bidirectional"))
    )
    (net (code "67") (name "Net-(Q5-PadD)") (class "Default")
      (node (ref "Q5") (pin "D") (pinfunction "D_D") (pintype "passive"))
      (node (ref "R29") (pin "2") (pinfunction "2_2") (pintype "bidirectional"))
    )
    (net (code "68") (name "Net-(Q5-PadG)") (class "Default")
      (node (ref "Q5") (pin "G") (pinfunction "G_G") (pintype "passive"))
      (node (ref "R32") (pin "1") (pinfunction "1_1") (pintype "bidirectional"))
      (node (ref "R34") (pin "2") (pinfunction "2_2") (pintype "bidirectional"))
    )
    (net (code "69") (name "Net-(R7-Pad2)") (class "Default")
      (node (ref "R7") (pin "2") (pinfunction "2_2") (pintype "bidirectional"))
      (node (ref "RCPWR") (pin "CATHODE") (pinfunction "CATHODE_CATHODE") (pintype "passive"))
    )
    (net (code "70") (name "Net-(U$9-4:Y)") (class "Default")
      (node (ref "LED1") (pin "SDI") (pinfunction "SDI_SDI") (pintype "bidirectional"))
      (node (ref "U$9") (pin "4") (pinfunction "4:Y_4") (pintype "output"))
    )
    (net (code "71") (name "Net-(U$10-4:Y)") (class "Default")
      (node (ref "LED1") (pin "CKI") (pinfunction "CKI_CKI") (pintype "bidirectional"))
      (node (ref "U$10") (pin "4") (pinfunction "4:Y_4") (pintype "output"))
    )
    (net (code "72") (name "Net-(U1-C)") (class "Default")
      (node (ref "R26") (pin "1") (pinfunction "1_1") (pintype "bidirectional"))
      (node (ref "U1") (pin "2") (pinfunction "C_2") (pintype "passive"))
    )
    (net (code "73") (name "Net-(U3-2:CA1)") (class "Default")
      (node (ref "R29") (pin "1") (pinfunction "1_1") (pintype "bidirectional"))
      (node (ref "U3") (pin "2") (pinfunction "2:CA1_2") (pintype "bidirectional"))
    )
    (net (code "74") (name "Net-(U3-3:CA2)") (class "Default")
      (node (ref "R27") (pin "1") (pinfunction "1_1") (pintype "bidirectional"))
      (node (ref "U3") (pin "3") (pinfunction "3:CA2_3") (pintype "bidirectional"))
    )
    (net (code "75") (name "Net-(U3-6:OUT2)") (class "Default")
      (node (ref "U2") (pin "P$16") (pinfunction "PA4_A1_D1_P$16") (pintype "bidirectional"))
      (node (ref "U2") (pin "P$2") (pinfunction "PA4_A1_D1_P$2") (pintype "bidirectional"))
      (node (ref "U3") (pin "6") (pinfunction "6:OUT2_6") (pintype "bidirectional"))
    )
    (net (code "76") (name "Net-(U3-7:OUT1)") (class "Default")
      (node (ref "U2") (pin "P$1") (pinfunction "PA02_A0_D0_P$1") (pintype "bidirectional"))
      (node (ref "U2") (pin "P$15") (pinfunction "PA02_A0_D0_P$15") (pintype "bidirectional"))
      (node (ref "U3") (pin "7") (pinfunction "7:OUT1_7") (pintype "bidirectional"))
    )
    (net (code "77") (name "Net-(U7-BS1)") (class "Default")
      (node (ref "R19") (pin "2") (pinfunction "2_2") (pintype "bidirectional"))
      (node (ref "U7") (pin "20") (pinfunction "BS1_20") (pintype "bidirectional"))
    )
    (net (code "78") (name "Net-(U7-C1N)") (class "Default")
      (node (ref "C19") (pin "1") (pinfunction "1_1") (pintype "passive"))
      (node (ref "U7") (pin "26") (pinfunction "C1N_26") (pintype "bidirectional"))
    )
    (net (code "79") (name "Net-(U7-C1P)") (class "Default")
      (node (ref "C19") (pin "2") (pinfunction "2_2") (pintype "passive"))
      (node (ref "U7") (pin "27") (pinfunction "C1P_27") (pintype "bidirectional"))
    )
    (net (code "80") (name "Net-(U7-C2N)") (class "Default")
      (node (ref "C22") (pin "1") (pinfunction "1_1") (pintype "passive"))
      (node (ref "U7") (pin "28") (pinfunction "C2N_28") (pintype "bidirectional"))
    )
    (net (code "81") (name "Net-(U7-C2P)") (class "Default")
      (node (ref "C22") (pin "2") (pinfunction "2_2") (pintype "passive"))
      (node (ref "U7") (pin "29") (pinfunction "C2P_29") (pintype "bidirectional"))
    )
    (net (code "82") (name "Net-(U7-D{slash}C#)") (class "Default")
      (node (ref "R36") (pin "2") (pinfunction "2_2") (pintype "bidirectional"))
      (node (ref "R37") (pin "1") (pinfunction "1_1") (pintype "bidirectional"))
      (node (ref "U7") (pin "16") (pinfunction "D/C#_16") (pintype "bidirectional"))
    )
    (net (code "83") (name "Net-(U7-IREF)") (class "Default")
      (node (ref "R13") (pin "1") (pinfunction "1_1") (pintype "bidirectional"))
      (node (ref "U7") (pin "5") (pinfunction "IREF_5") (pintype "bidirectional"))
    )
    (net (code "84") (name "Net-(U7-RES#)") (class "Default")
      (node (ref "R31") (pin "2") (pinfunction "2_2") (pintype "bidirectional"))
      (node (ref "U7") (pin "17") (pinfunction "RES#_17") (pintype "bidirectional"))
    )
    (net (code "85") (name "Net-(U7-VCC)") (class "Default")
      (node (ref "C13") (pin "2") (pinfunction "2_2") (pintype "passive"))
      (node (ref "U7") (pin "3") (pinfunction "VCC_3") (pintype "bidirectional"))
    )
    (net (code "86") (name "Net-(U7-VCOMH)") (class "Default")
      (node (ref "C16") (pin "2") (pinfunction "2_2") (pintype "passive"))
      (node (ref "U7") (pin "4") (pinfunction "VCOMH_4") (pintype "bidirectional"))
    )
    (net (code "87") (name "XAIO_5V") (class "Default")
      (node (ref "D3") (pin "K") (pinfunction "CATHODE_K") (pintype "passive"))
      (node (ref "U2") (pin "P$14") (pinfunction "5V_P$14") (pintype "bidirectional"))
      (node (ref "U2") (pin "P$28") (pinfunction "5V_P$28") (pintype "bidirectional"))
    )
    (net (code "88") (name "XIAO_3V3") (class "Default")
      (node (ref "U2") (pin "P$12") (pinfunction "3V3_P$12") (pintype "bidirectional"))
      (node (ref "U2") (pin "P$26") (pinfunction "3V3_P$26") (pintype "bidirectional"))
    )
    (net (code "89") (name "unconnected-(GPIO40-CE1-Pad26)") (class "Default")
      (node (ref "GPIO40") (pin "26") (pinfunction "CE1_26") (pintype "bidirectional"))
    )
    (net (code "90") (name "unconnected-(GPIO40-ID_SC-Pad28)") (class "Default")
      (node (ref "GPIO40") (pin "28") (pinfunction "ID_SC_28") (pintype "bidirectional"))
    )
    (net (code "91") (name "unconnected-(GPIO40-ID_SD-Pad27)") (class "Default")
      (node (ref "GPIO40") (pin "27") (pinfunction "ID_SD_27") (pintype "bidirectional"))
    )
    (net (code "92") (name "unconnected-(IC2-LED2-Pad8)") (class "Default")
      (node (ref "IC2") (pin "8") (pinfunction "LED2_8") (pintype "bidirectional"))
    )
    (net (code "93") (name "unconnected-(IC2-LED3-Pad9)") (class "Default")
      (node (ref "IC2") (pin "9") (pinfunction "LED3_9") (pintype "bidirectional"))
    )
    (net (code "94") (name "unconnected-(IC2-LED4-Pad10)") (class "Default")
      (node (ref "IC2") (pin "10") (pinfunction "LED4_10") (pintype "bidirectional"))
    )
    (net (code "95") (name "unconnected-(IC2-LED5-Pad11)") (class "Default")
      (node (ref "IC2") (pin "11") (pinfunction "LED5_11") (pintype "bidirectional"))
    )
    (net (code "96") (name "unconnected-(IC2-LED6-Pad12)") (class "Default")
      (node (ref "IC2") (pin "12") (pinfunction "LED6_12") (pintype "bidirectional"))
    )
    (net (code "97") (name "unconnected-(IC2-LED7-Pad13)") (class "Default")
      (node (ref "IC2") (pin "13") (pinfunction "LED7_13") (pintype "bidirectional"))
    )
    (net (code "98") (name "unconnected-(IC2-LED8-Pad15)") (class "Default")
      (node (ref "IC2") (pin "15") (pinfunction "LED8_15") (pintype "bidirectional"))
    )
    (net (code "99") (name "unconnected-(IC2-LED9-Pad16)") (class "Default")
      (node (ref "IC2") (pin "16") (pinfunction "LED9_16") (pintype "bidirectional"))
    )
    (net (code "100") (name "unconnected-(IC2-LED10-Pad17)") (class "Default")
      (node (ref "IC2") (pin "17") (pinfunction "LED10_17") (pintype "bidirectional"))
    )
    (net (code "101") (name "unconnected-(IC2-LED11-Pad18)") (class "Default")
      (node (ref "IC2") (pin "18") (pinfunction "LED11_18") (pintype "bidirectional"))
    )
    (net (code "102") (name "unconnected-(IC2-LED12-Pad19)") (class "Default")
      (node (ref "IC2") (pin "19") (pinfunction "LED12_19") (pintype "bidirectional"))
    )
    (net (code "103") (name "unconnected-(IC2-LED13-Pad20)") (class "Default")
      (node (ref "IC2") (pin "20") (pinfunction "LED13_20") (pintype "bidirectional"))
    )
    (net (code "104") (name "unconnected-(IC2-LED14-Pad21)") (class "Default")
      (node (ref "IC2") (pin "21") (pinfunction "LED14_21") (pintype "bidirectional"))
    )
    (net (code "105") (name "unconnected-(IC2-LED15-Pad22)") (class "Default")
      (node (ref "IC2") (pin "22") (pinfunction "LED15_22") (pintype "bidirectional"))
    )
    (net (code "106") (name "unconnected-(U$3-9:Y2-Pad9)") (class "Default")
      (node (ref "U$3") (pin "9") (pinfunction "9:Y2_9") (pintype "bidirectional"))
    )
    (net (code "107") (name "unconnected-(U$3-10:B2-Pad10)") (class "Default")
      (node (ref "U$3") (pin "10") (pinfunction "10:B2_10") (pintype "bidirectional"))
    )
    (net (code "108") (name "unconnected-(U$3-11:A2-Pad11)") (class "Default")
      (node (ref "U$3") (pin "11") (pinfunction "11:A2_11") (pintype "bidirectional"))
    )
    (net (code "109") (name "unconnected-(U$3-12:Y3-Pad12)") (class "Default")
      (node (ref "U$3") (pin "12") (pinfunction "12:Y3_12") (pintype "bidirectional"))
    )
    (net (code "110") (name "unconnected-(U$3-13:B3-Pad13)") (class "Default")
      (node (ref "U$3") (pin "13") (pinfunction "13:B3_13") (pintype "bidirectional"))
    )
    (net (code "111") (name "unconnected-(U$3-14:A3-Pad14)") (class "Default")
      (node (ref "U$3") (pin "14") (pinfunction "14:A3_14") (pintype "bidirectional"))
    )
    (net (code "112") (name "unconnected-(U7-NC-Pad1)") (class "Default")
      (node (ref "U7") (pin "1") (pinfunction "NC_1") (pintype "bidirectional"))
    )
    (net (code "113") (name "unconnected-(U7-NC-Pad24)") (class "Default")
      (node (ref "U7") (pin "24") (pinfunction "NC_24") (pintype "bidirectional"))
    )
    (net (code "114") (name "unconnected-(U7-NC-Pad30)") (class "Default")
      (node (ref "U7") (pin "30") (pinfunction "NC_30") (pintype "bidirectional"))
    )
  )
)
